# lcd_pin.net
KiCad netlist of a schematic drawn in Altium Designer
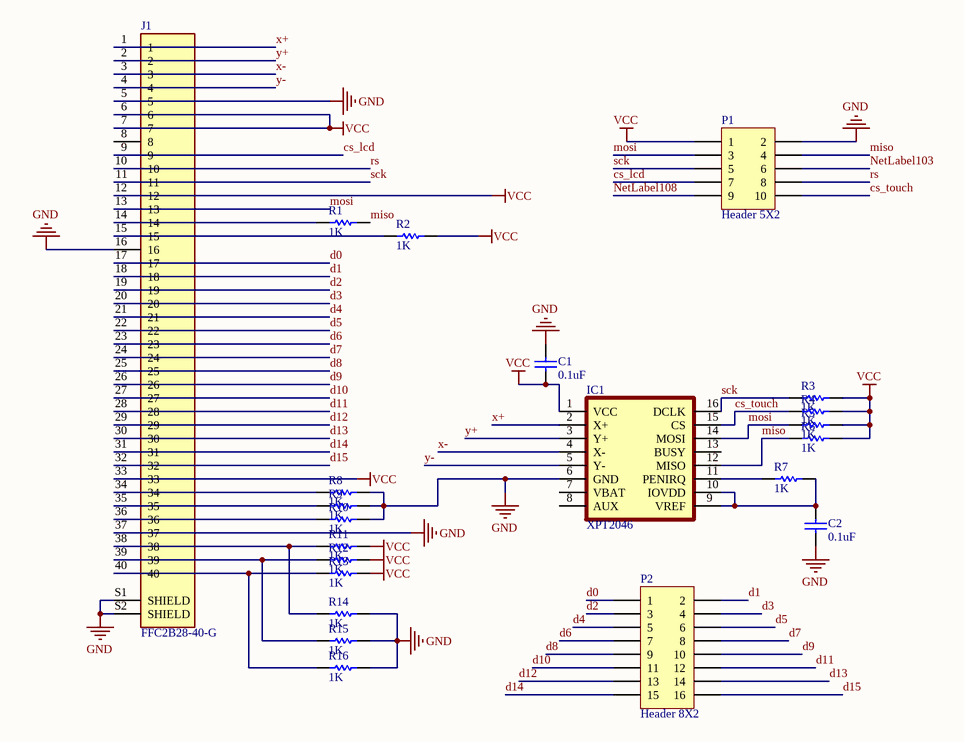
[diagram p0: lcd_pin.SchDoc]

(export (version "E")
  (design (tool "Eeschema 10.0.6"))
  (components
    (comp (ref "C1")
      (value "0.1uF")
      (footprint "CAPC4817X12N")
      (description "CAP 1206")
      (fields (field (name "DESIGNER") "Abbas Basereh"))
      (libsource (lib "Altium") (part "CAP SMD 1206"))
    )
    (comp (ref "C2")
      (value "0.1uF")
      (footprint "CAPC4817X12N")
      (description "CAP 1206")
      (fields (field (name "DESIGNER") "Abbas Basereh"))
      (libsource (lib "Altium") (part "CAP SMD 1206"))
    )
    (comp (ref "IC1")
      (value "XPT2046")
      (footprint "TSSOP16")
      (description "RASPBERRY PI 3.5 TFT DISPLAY")
      (fields (field (name "MF") "Xptek"))
      (libsource (lib "XPT2046") (part "XPT2046"))
    )
    (comp (ref "J1")
      (value "FFC2B28-40-G")
      (footprint "GCT_FFC2B28-40-G")
      (description "40 Position FFC, FPC Connector Contacts, Top and Bottom 0.020 _0.50mm_ Surface Mount, Right Angle")
      (fields (field (name "MF") "Global Connector Technology"))
      (libsource (lib "FFC2B28-40-G") (part "FFC2B28-40-G"))
    )
    (comp (ref "P1")
      (value "Header 5X2")
      (footprint "HDR2X5")
      (description "Header, 5-Pin, Dual row")
      (fields (field (name "PUBLISHER") "Altium Limited"))
      (libsource (lib "Miscellaneous Connectors") (part "Header 5X2"))
    )
    (comp (ref "P2")
      (value "Header 8X2")
      (footprint "HDR2X8")
      (description "Header, 8-Pin, Dual row")
      (fields (field (name "PUBLISHER") "Altium Limited"))
      (libsource (lib "Miscellaneous Connectors") (part "Header 8X2"))
    )
    (comp (ref "R1")
      (value "1K")
      (footprint "RESC4817X04N")
      (description "RES 1206")
      (fields (field (name "DESIGNER") "Abbas Basereh"))
      (libsource (lib "Altium") (part "RES 1206 0.25W"))
    )
    (comp (ref "R2")
      (value "1K")
      (footprint "RESC4817X04N")
      (description "RES 1206")
      (fields (field (name "DESIGNER") "Abbas Basereh"))
      (libsource (lib "Altium") (part "RES 1206 0.25W"))
    )
    (comp (ref "R3")
      (value "1K")
      (footprint "RESC4817X04N")
      (description "RES 1206")
      (fields (field (name "DESIGNER") "Abbas Basereh"))
      (libsource (lib "Altium") (part "RES 1206 0.25W"))
    )
    (comp (ref "R4")
      (value "1K")
      (footprint "RESC4817X04N")
      (description "RES 1206")
      (fields (field (name "DESIGNER") "Abbas Basereh"))
      (libsource (lib "Altium") (part "RES 1206 0.25W"))
    )
    (comp (ref "R5")
      (value "1K")
      (footprint "RESC4817X04N")
      (description "RES 1206")
      (fields (field (name "DESIGNER") "Abbas Basereh"))
      (libsource (lib "Altium") (part "RES 1206 0.25W"))
    )
    (comp (ref "R6")
      (value "1K")
      (footprint "RESC4817X04N")
      (description "RES 1206")
      (fields (field (name "DESIGNER") "Abbas Basereh"))
      (libsource (lib "Altium") (part "RES 1206 0.25W"))
    )
    (comp (ref "R7")
      (value "1K")
      (footprint "RESC4817X04N")
      (description "RES 1206")
      (fields (field (name "DESIGNER") "Abbas Basereh"))
      (libsource (lib "Altium") (part "RES 1206 0.25W"))
    )
    (comp (ref "R8")
      (value "1K")
      (footprint "RESC4817X04N")
      (description "RES 1206")
      (fields (field (name "DESIGNER") "Abbas Basereh"))
      (libsource (lib "Altium") (part "RES 1206 0.25W"))
    )
    (comp (ref "R9")
      (value "1K")
      (footprint "RESC4817X04N")
      (description "RES 1206")
      (fields (field (name "DESIGNER") "Abbas Basereh"))
      (libsource (lib "Altium") (part "RES 1206 0.25W"))
    )
    (comp (ref "R10")
      (value "1K")
      (footprint "RESC4817X04N")
      (description "RES 1206")
      (fields (field (name "DESIGNER") "Abbas Basereh"))
      (libsource (lib "Altium") (part "RES 1206 0.25W"))
    )
    (comp (ref "R11")
      (value "1K")
      (footprint "RESC4817X04N")
      (description "RES 1206")
      (fields (field (name "DESIGNER") "Abbas Basereh"))
      (libsource (lib "Altium") (part "RES 1206 0.25W"))
    )
    (comp (ref "R12")
      (value "1K")
      (footprint "RESC4817X04N")
      (description "RES 1206")
      (fields (field (name "DESIGNER") "Abbas Basereh"))
      (libsource (lib "Altium") (part "RES 1206 0.25W"))
    )
    (comp (ref "R13")
      (value "1K")
      (footprint "RESC4817X04N")
      (description "RES 1206")
      (fields (field (name "DESIGNER") "Abbas Basereh"))
      (libsource (lib "Altium") (part "RES 1206 0.25W"))
    )
    (comp (ref "R14")
      (value "1K")
      (footprint "RESC4817X04N")
      (description "RES 1206")
      (fields (field (name "DESIGNER") "Abbas Basereh"))
      (libsource (lib "Altium") (part "RES 1206 0.25W"))
    )
    (comp (ref "R15")
      (value "1K")
      (footprint "RESC4817X04N")
      (description "RES 1206")
      (fields (field (name "DESIGNER") "Abbas Basereh"))
      (libsource (lib "Altium") (part "RES 1206 0.25W"))
    )
    (comp (ref "R16")
      (value "1K")
      (footprint "RESC4817X04N")
      (description "RES 1206")
      (fields (field (name "DESIGNER") "Abbas Basereh"))
      (libsource (lib "Altium") (part "RES 1206 0.25W"))
    )
  )
  (nets
    (net (code "1") (name "/NetLabel103") (class "Default")
      (node (ref "P1") (pin "6") (pinfunction "6_6") (pintype "passive"))
    )
    (net (code "2") (name "/NetLabel108") (class "Default")
      (node (ref "P1") (pin "9") (pinfunction "9_9") (pintype "passive"))
    )
    (net (code "3") (name "/cs_lcd") (class "Default")
      (node (ref "J1") (pin "9") (pinfunction "9_9") (pintype "passive"))
      (node (ref "P1") (pin "7") (pinfunction "7_7") (pintype "passive"))
    )
    (net (code "4") (name "/cs_touch") (class "Default")
      (node (ref "IC1") (pin "15") (pinfunction "CS_15") (pintype "passive"))
      (node (ref "P1") (pin "10") (pinfunction "10_10") (pintype "passive"))
      (node (ref "R4") (pin "1") (pinfunction "1_1") (pintype "passive"))
    )
    (net (code "5") (name "/d0") (class "Default")
      (node (ref "J1") (pin "17") (pinfunction "17_17") (pintype "passive"))
      (node (ref "P2") (pin "1") (pinfunction "1_1") (pintype "passive"))
    )
    (net (code "6") (name "/d1") (class "Default")
      (node (ref "J1") (pin "18") (pinfunction "18_18") (pintype "passive"))
      (node (ref "P2") (pin "2") (pinfunction "2_2") (pintype "passive"))
    )
    (net (code "7") (name "/d2") (class "Default")
      (node (ref "J1") (pin "19") (pinfunction "19_19") (pintype "passive"))
      (node (ref "P2") (pin "3") (pinfunction "3_3") (pintype "passive"))
    )
    (net (code "8") (name "/d3") (class "Default")
      (node (ref "J1") (pin "20") (pinfunction "20_20") (pintype "passive"))
      (node (ref "P2") (pin "4") (pinfunction "4_4") (pintype "passive"))
    )
    (net (code "9") (name "/d4") (class "Default")
      (node (ref "J1") (pin "21") (pinfunction "21_21") (pintype "passive"))
      (node (ref "P2") (pin "5") (pinfunction "5_5") (pintype "passive"))
    )
    (net (code "10") (name "/d5") (class "Default")
      (node (ref "J1") (pin "22") (pinfunction "22_22") (pintype "passive"))
      (node (ref "P2") (pin "6") (pinfunction "6_6") (pintype "passive"))
    )
    (net (code "11") (name "/d6") (class "Default")
      (node (ref "J1") (pin "23") (pinfunction "23_23") (pintype "passive"))
      (node (ref "P2") (pin "7") (pinfunction "7_7") (pintype "passive"))
    )
    (net (code "12") (name "/d7") (class "Default")
      (node (ref "J1") (pin "24") (pinfunction "24_24") (pintype "passive"))
      (node (ref "P2") (pin "8") (pinfunction "8_8") (pintype "passive"))
    )
    (net (code "13") (name "/d8") (class "Default")
      (node (ref "J1") (pin "25") (pinfunction "25_25") (pintype "passive"))
      (node (ref "P2") (pin "9") (pinfunction "9_9") (pintype "passive"))
    )
    (net (code "14") (name "/d9") (class "Default")
      (node (ref "J1") (pin "26") (pinfunction "26_26") (pintype "passive"))
      (node (ref "P2") (pin "10") (pinfunction "10_10") (pintype "passive"))
    )
    (net (code "15") (name "/d10") (class "Default")
      (node (ref "J1") (pin "27") (pinfunction "27_27") (pintype "passive"))
      (node (ref "P2") (pin "11") (pinfunction "11_11") (pintype "passive"))
    )
    (net (code "16") (name "/d11") (class "Default")
      (node (ref "J1") (pin "28") (pinfunction "28_28") (pintype "passive"))
      (node (ref "P2") (pin "12") (pinfunction "12_12") (pintype "passive"))
    )
    (net (code "17") (name "/d12") (class "Default")
      (node (ref "J1") (pin "29") (pinfunction "29_29") (pintype "passive"))
      (node (ref "P2") (pin "13") (pinfunction "13_13") (pintype "passive"))
    )
    (net (code "18") (name "/d13") (class "Default")
      (node (ref "J1") (pin "30") (pinfunction "30_30") (pintype "passive"))
      (node (ref "P2") (pin "14") (pinfunction "14_14") (pintype "passive"))
    )
    (net (code "19") (name "/d14") (class "Default")
      (node (ref "J1") (pin "31") (pinfunction "31_31") (pintype "passive"))
      (node (ref "P2") (pin "15") (pinfunction "15_15") (pintype "passive"))
    )
    (net (code "20") (name "/d15") (class "Default")
      (node (ref "J1") (pin "32") (pinfunction "32_32") (pintype "passive"))
      (node (ref "P2") (pin "16") (pinfunction "16_16") (pintype "passive"))
    )
    (net (code "21") (name "/miso") (class "Default")
      (node (ref "IC1") (pin "12") (pinfunction "MISO_12") (pintype "passive"))
      (node (ref "P1") (pin "4") (pinfunction "4_4") (pintype "passive"))
      (node (ref "R1") (pin "2") (pinfunction "2_2") (pintype "passive"))
      (node (ref "R6") (pin "1") (pinfunction "1_1") (pintype "passive"))
    )
    (net (code "22") (name "/mosi") (class "Default")
      (node (ref "IC1") (pin "14") (pinfunction "MOSI_14") (pintype "passive"))
      (node (ref "J1") (pin "13") (pinfunction "13_13") (pintype "passive"))
      (node (ref "P1") (pin "3") (pinfunction "3_3") (pintype "passive"))
      (node (ref "R5") (pin "1") (pinfunction "1_1") (pintype "passive"))
    )
    (net (code "23") (name "/rs") (class "Default")
      (node (ref "J1") (pin "10") (pinfunction "10_10") (pintype "passive"))
      (node (ref "P1") (pin "8") (pinfunction "8_8") (pintype "passive"))
    )
    (net (code "24") (name "/sck") (class "Default")
      (node (ref "IC1") (pin "16") (pinfunction "DCLK_16") (pintype "passive"))
      (node (ref "J1") (pin "11") (pinfunction "11_11") (pintype "passive"))
      (node (ref "P1") (pin "5") (pinfunction "5_5") (pintype "passive"))
      (node (ref "R3") (pin "1") (pinfunction "1_1") (pintype "passive"))
    )
    (net (code "25") (name "/x+") (class "Default")
      (node (ref "IC1") (pin "2") (pinfunction "X+_2") (pintype "passive"))
      (node (ref "J1") (pin "1") (pinfunction "1_1") (pintype "passive"))
    )
    (net (code "26") (name "/x-") (class "Default")
      (node (ref "IC1") (pin "4") (pinfunction "X-_4") (pintype "passive"))
      (node (ref "J1") (pin "3") (pinfunction "3_3") (pintype "passive"))
    )
    (net (code "27") (name "/y+") (class "Default")
      (node (ref "IC1") (pin "3") (pinfunction "Y+_3") (pintype "passive"))
      (node (ref "J1") (pin "2") (pinfunction "2_2") (pintype "passive"))
    )
    (net (code "28") (name "/y-") (class "Default")
      (node (ref "IC1") (pin "5") (pinfunction "Y-_5") (pintype "passive"))
      (node (ref "J1") (pin "4") (pinfunction "4_4") (pintype "passive"))
    )
    (net (code "29") (name "GND") (class "Default")
      (node (ref "C1") (pin "2") (pinfunction "2_2") (pintype "passive"))
      (node (ref "C2") (pin "1") (pinfunction "1_1") (pintype "passive"))
      (node (ref "IC1") (pin "6") (pinfunction "GND_6") (pintype "passive"))
      (node (ref "J1") (pin "16") (pinfunction "16_16") (pintype "passive"))
      (node (ref "J1") (pin "37") (pinfunction "37_37") (pintype "passive"))
      (node (ref "J1") (pin "5") (pinfunction "5_5") (pintype "passive"))
      (node (ref "J1") (pin "S1") (pinfunction "SHIELD_S1") (pintype "passive"))
      (node (ref "J1") (pin "S2") (pinfunction "SHIELD_S2") (pintype "passive"))
      (node (ref "P1") (pin "2") (pinfunction "2_2") (pintype "passive"))
      (node (ref "R10") (pin "2") (pinfunction "2_2") (pintype "passive"))
      (node (ref "R14") (pin "2") (pinfunction "2_2") (pintype "passive"))
      (node (ref "R15") (pin "2") (pinfunction "2_2") (pintype "passive"))
      (node (ref "R16") (pin "2") (pinfunction "2_2") (pintype "passive"))
      (node (ref "R8") (pin "2") (pinfunction "2_2") (pintype "passive"))
      (node (ref "R9") (pin "2") (pinfunction "2_2") (pintype "passive"))
    )
    (net (code "30") (name "Net-(IC1-IOVDD)") (class "Default")
      (node (ref "C2") (pin "2") (pinfunction "2_2") (pintype "passive"))
      (node (ref "IC1") (pin "10") (pinfunction "IOVDD_10") (pintype "passive"))
      (node (ref "IC1") (pin "9") (pinfunction "VREF_9") (pintype "passive"))
      (node (ref "R7") (pin "2") (pinfunction "2_2") (pintype "passive"))
    )
    (net (code "31") (name "Net-(IC1-PENIRQ)") (class "Default")
      (node (ref "IC1") (pin "11") (pinfunction "PENIRQ_11") (pintype "passive"))
      (node (ref "R7") (pin "1") (pinfunction "1_1") (pintype "passive"))
    )
    (net (code "32") (name "Net-(J1-Pad14)") (class "Default")
      (node (ref "J1") (pin "14") (pinfunction "14_14") (pintype "passive"))
      (node (ref "R1") (pin "1") (pinfunction "1_1") (pintype "passive"))
    )
    (net (code "33") (name "Net-(J1-Pad15)") (class "Default")
      (node (ref "J1") (pin "15") (pinfunction "15_15") (pintype "passive"))
      (node (ref "R2") (pin "1") (pinfunction "1_1") (pintype "passive"))
    )
    (net (code "34") (name "Net-(J1-Pad34)") (class "Default")
      (node (ref "J1") (pin "34") (pinfunction "34_34") (pintype "passive"))
      (node (ref "R8") (pin "1") (pinfunction "1_1") (pintype "passive"))
    )
    (net (code "35") (name "Net-(J1-Pad35)") (class "Default")
      (node (ref "J1") (pin "35") (pinfunction "35_35") (pintype "passive"))
      (node (ref "R9") (pin "1") (pinfunction "1_1") (pintype "passive"))
    )
    (net (code "36") (name "Net-(J1-Pad36)") (class "Default")
      (node (ref "J1") (pin "36") (pinfunction "36_36") (pintype "passive"))
      (node (ref "R10") (pin "1") (pinfunction "1_1") (pintype "passive"))
    )
    (net (code "37") (name "Net-(J1-Pad38)") (class "Default")
      (node (ref "J1") (pin "38") (pinfunction "38_38") (pintype "passive"))
      (node (ref "R11") (pin "1") (pinfunction "1_1") (pintype "passive"))
      (node (ref "R14") (pin "1") (pinfunction "1_1") (pintype "passive"))
    )
    (net (code "38") (name "Net-(J1-Pad39)") (class "Default")
      (node (ref "J1") (pin "39") (pinfunction "39_39") (pintype "passive"))
      (node (ref "R12") (pin "1") (pinfunction "1_1") (pintype "passive"))
      (node (ref "R15") (pin "1") (pinfunction "1_1") (pintype "passive"))
    )
    (net (code "39") (name "Net-(J1-Pad40)") (class "Default")
      (node (ref "J1") (pin "40") (pinfunction "40_40") (pintype "passive"))
      (node (ref "R13") (pin "1") (pinfunction "1_1") (pintype "passive"))
      (node (ref "R16") (pin "1") (pinfunction "1_1") (pintype "passive"))
    )
    (net (code "40") (name "VCC") (class "Default")
      (node (ref "C1") (pin "1") (pinfunction "1_1") (pintype "passive"))
      (node (ref "IC1") (pin "1") (pinfunction "VCC_1") (pintype "passive"))
      (node (ref "J1") (pin "12") (pinfunction "12_12") (pintype "passive"))
      (node (ref "J1") (pin "33") (pinfunction "33_33") (pintype "passive"))
      (node (ref "J1") (pin "6") (pinfunction "6_6") (pintype "passive"))
      (node (ref "J1") (pin "7") (pinfunction "7_7") (pintype "passive"))
      (node (ref "P1") (pin "1") (pinfunction "1_1") (pintype "passive"))
      (node (ref "R11") (pin "2") (pinfunction "2_2") (pintype "passive"))
      (node (ref "R12") (pin "2") (pinfunction "2_2") (pintype "passive"))
      (node (ref "R13") (pin "2") (pinfunction "2_2") (pintype "passive"))
      (node (ref "R2") (pin "2") (pinfunction "2_2") (pintype "passive"))
      (node (ref "R3") (pin "2") (pinfunction "2_2") (pintype "passive"))
      (node (ref "R4") (pin "2") (pinfunction "2_2") (pintype "passive"))
      (node (ref "R5") (pin "2") (pinfunction "2_2") (pintype "passive"))
      (node (ref "R6") (pin "2") (pinfunction "2_2") (pintype "passive"))
    )
    (net (code "41") (name "unconnected-(IC1-AUX-Pad8)") (class "Default")
      (node (ref "IC1") (pin "8") (pinfunction "AUX_8") (pintype "passive"))
    )
    (net (code "42") (name "unconnected-(IC1-BUSY-Pad13)") (class "Default")
      (node (ref "IC1") (pin "13") (pinfunction "BUSY_13") (pintype "passive"))
    )
    (net (code "43") (name "unconnected-(IC1-VBAT-Pad7)") (class "Default")
      (node (ref "IC1") (pin "7") (pinfunction "VBAT_7") (pintype "passive"))
    )
    (net (code "44") (name "unconnected-(J1-Pad8)") (class "Default")
      (node (ref "J1") (pin "8") (pinfunction "8_8") (pintype "passive"))
    )
  )
)
